# pcb10_5.net
KiCad netlist of a schematic drawn in EAGLE
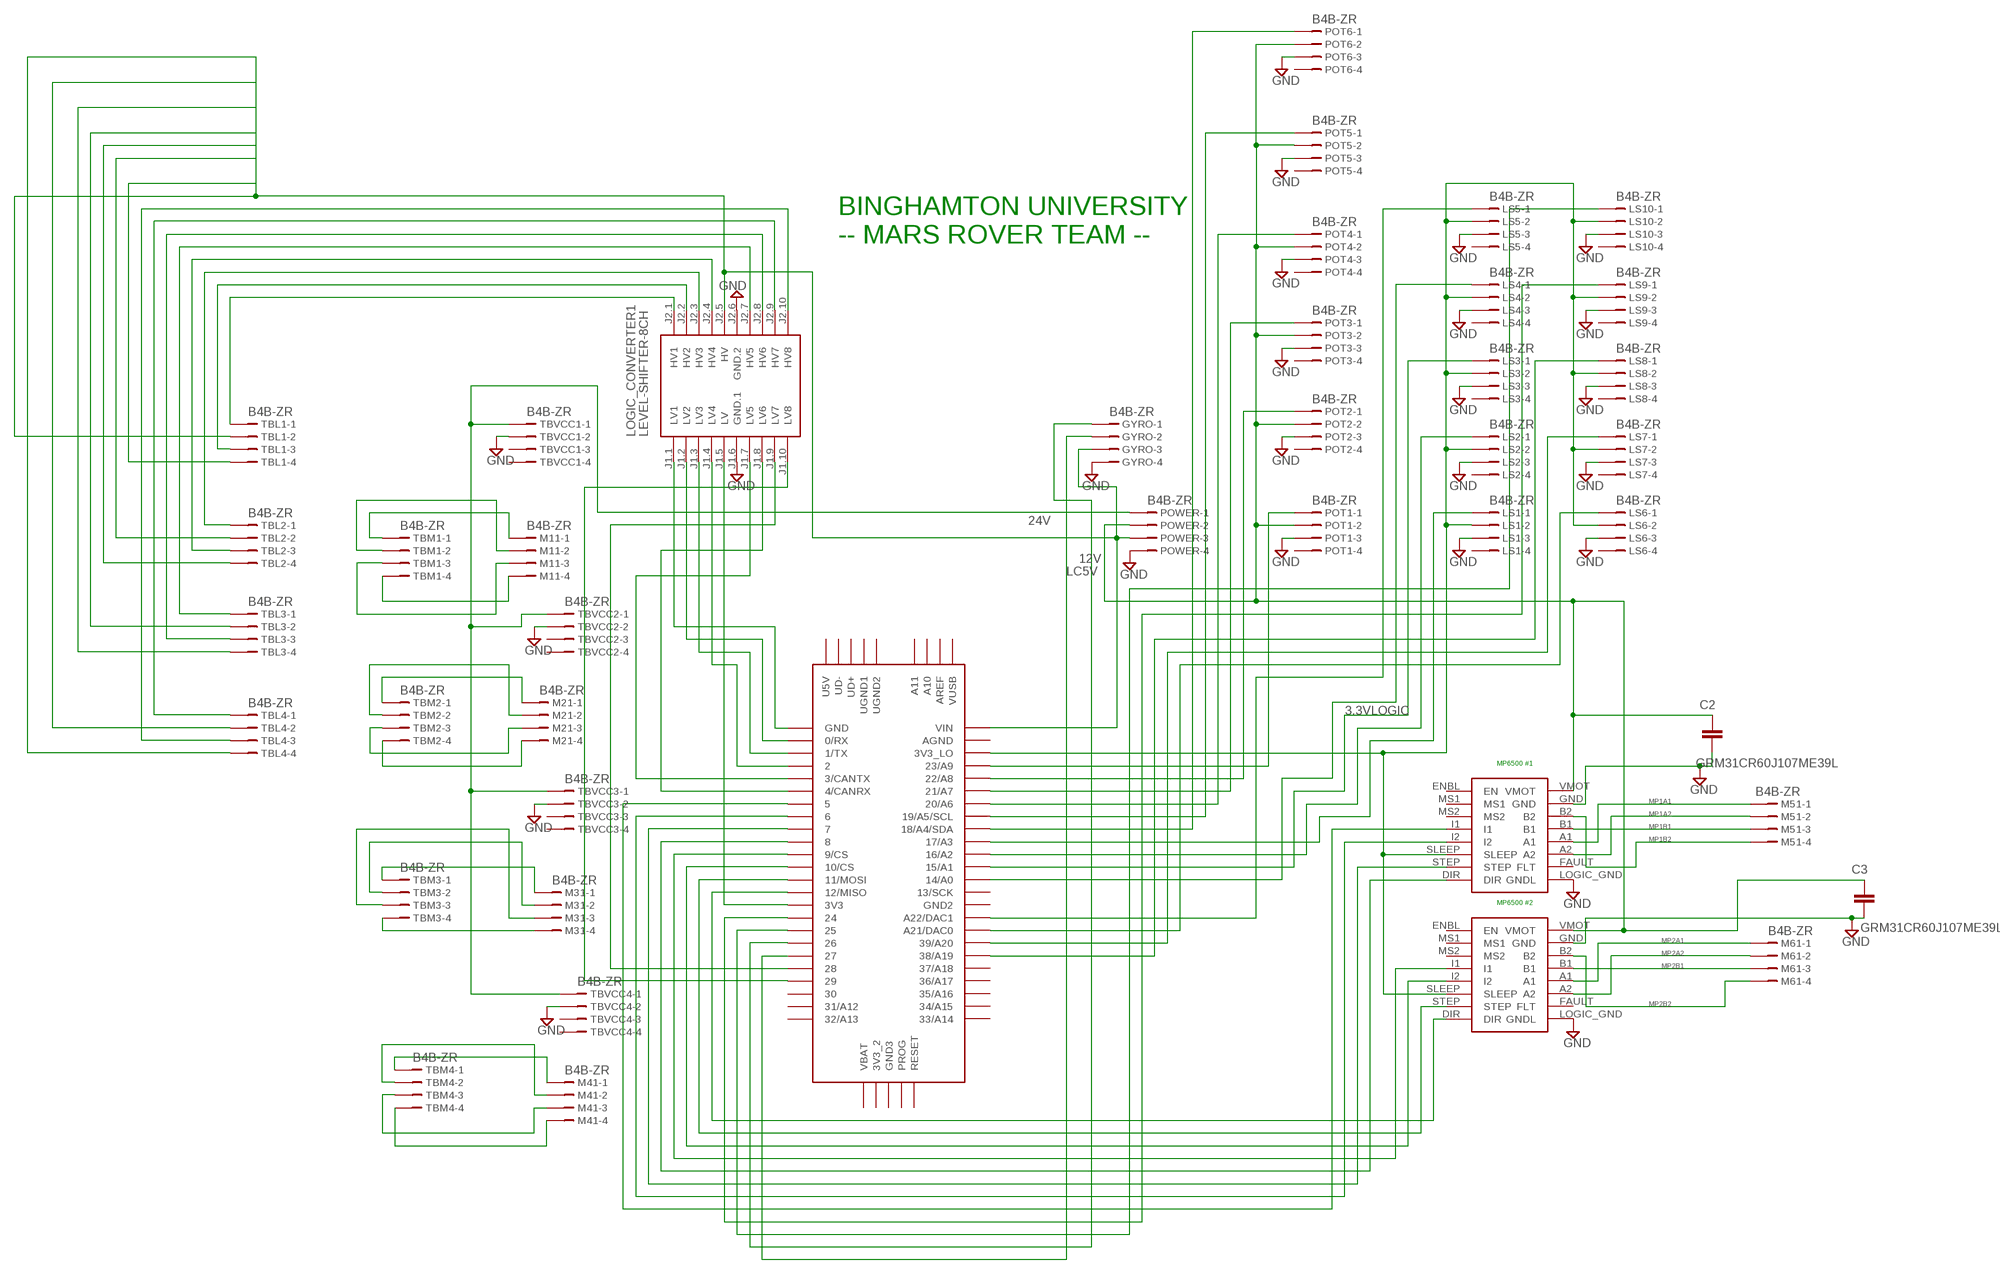
[diagram p0: schematic, sheet 1]

(export (version "E")
  (design (tool "Eeschema 10.0.6"))
  (components
    (comp (ref "C2")
      (value "GRM31CR60J107ME39L")
      (footprint "eagle-import:CAP_1206")
      (fields
        (field (name "MANUFACTURER") "Murata Electronics North America")
        (field (name "CREATED_BY") "PCBLayout.com")
      )
      (libsource (lib "eagle-import") (part "GRM31CR60J107ME39L"))
    )
    (comp (ref "C3")
      (value "GRM31CR60J107ME39L")
      (footprint "eagle-import:CAP_1206")
      (fields
        (field (name "MANUFACTURER") "Murata Electronics North America")
        (field (name "CREATED_BY") "PCBLayout.com")
      )
      (libsource (lib "eagle-import") (part "GRM31CR60J107ME39L"))
    )
    (comp (ref "GYRO")
      (value "B4B-ZR")
      (footprint "eagle-import:B4B-ZR")
      (fields (field (name "MF") "FARNELL") (field (name "MPN") "B4B-ZR(LF)(SN)"))
      (libsource (lib "eagle-import") (part "?4B-ZRB"))
    )
    (comp (ref "LOGIC_CONVERTER1")
      (value "LEVEL-SHIFTER-8CH")
      (footprint "eagle-import:LEVEL-SHIFTER-8CH")
      (libsource (lib "eagle-import") (part "LEVEL-SHIFTER-8CH"))
    )
    (comp (ref "LS1")
      (value "B4B-ZR")
      (footprint "eagle-import:B4B-ZR")
      (fields (field (name "MF") "FARNELL") (field (name "MPN") "B4B-ZR(LF)(SN)"))
      (libsource (lib "eagle-import") (part "?4B-ZRB"))
    )
    (comp (ref "LS2")
      (value "B4B-ZR")
      (footprint "eagle-import:B4B-ZR")
      (fields (field (name "MF") "FARNELL") (field (name "MPN") "B4B-ZR(LF)(SN)"))
      (libsource (lib "eagle-import") (part "?4B-ZRB"))
    )
    (comp (ref "LS3")
      (value "B4B-ZR")
      (footprint "eagle-import:B4B-ZR")
      (fields (field (name "MF") "FARNELL") (field (name "MPN") "B4B-ZR(LF)(SN)"))
      (libsource (lib "eagle-import") (part "?4B-ZRB"))
    )
    (comp (ref "LS4")
      (value "B4B-ZR")
      (footprint "eagle-import:B4B-ZR")
      (fields (field (name "MF") "FARNELL") (field (name "MPN") "B4B-ZR(LF)(SN)"))
      (libsource (lib "eagle-import") (part "?4B-ZRB"))
    )
    (comp (ref "LS5")
      (value "B4B-ZR")
      (footprint "eagle-import:B4B-ZR")
      (fields (field (name "MF") "FARNELL") (field (name "MPN") "B4B-ZR(LF)(SN)"))
      (libsource (lib "eagle-import") (part "?4B-ZRB"))
    )
    (comp (ref "LS6")
      (value "B4B-ZR")
      (footprint "eagle-import:B4B-ZR")
      (fields (field (name "MF") "FARNELL") (field (name "MPN") "B4B-ZR(LF)(SN)"))
      (libsource (lib "eagle-import") (part "?4B-ZRB"))
    )
    (comp (ref "LS7")
      (value "B4B-ZR")
      (footprint "eagle-import:B4B-ZR")
      (fields (field (name "MF") "FARNELL") (field (name "MPN") "B4B-ZR(LF)(SN)"))
      (libsource (lib "eagle-import") (part "?4B-ZRB"))
    )
    (comp (ref "LS8")
      (value "B4B-ZR")
      (footprint "eagle-import:B4B-ZR")
      (fields (field (name "MF") "FARNELL") (field (name "MPN") "B4B-ZR(LF)(SN)"))
      (libsource (lib "eagle-import") (part "?4B-ZRB"))
    )
    (comp (ref "LS9")
      (value "B4B-ZR")
      (footprint "eagle-import:B4B-ZR")
      (fields (field (name "MF") "FARNELL") (field (name "MPN") "B4B-ZR(LF)(SN)"))
      (libsource (lib "eagle-import") (part "?4B-ZRB"))
    )
    (comp (ref "LS10")
      (value "B4B-ZR")
      (footprint "eagle-import:B4B-ZR")
      (fields (field (name "MF") "FARNELL") (field (name "MPN") "B4B-ZR(LF)(SN)"))
      (libsource (lib "eagle-import") (part "?4B-ZRB"))
    )
    (comp (ref "M11")
      (value "B4B-ZR")
      (footprint "eagle-import:B4B-ZR")
      (fields (field (name "MF") "FARNELL") (field (name "MPN") "B4B-ZR(LF)(SN)"))
      (libsource (lib "eagle-import") (part "?4B-ZRB"))
    )
    (comp (ref "M21")
      (value "B4B-ZR")
      (footprint "eagle-import:B4B-ZR")
      (fields (field (name "MF") "FARNELL") (field (name "MPN") "B4B-ZR(LF)(SN)"))
      (libsource (lib "eagle-import") (part "?4B-ZRB"))
    )
    (comp (ref "M31")
      (value "B4B-ZR")
      (footprint "eagle-import:B4B-ZR")
      (fields (field (name "MF") "FARNELL") (field (name "MPN") "B4B-ZR(LF)(SN)"))
      (libsource (lib "eagle-import") (part "?4B-ZRB"))
    )
    (comp (ref "M41")
      (value "B4B-ZR")
      (footprint "eagle-import:B4B-ZR")
      (fields (field (name "MF") "FARNELL") (field (name "MPN") "B4B-ZR(LF)(SN)"))
      (libsource (lib "eagle-import") (part "?4B-ZRB"))
    )
    (comp (ref "M51")
      (value "B4B-ZR")
      (footprint "eagle-import:B4B-ZR")
      (fields (field (name "MF") "FARNELL") (field (name "MPN") "B4B-ZR(LF)(SN)"))
      (libsource (lib "eagle-import") (part "?4B-ZRB"))
    )
    (comp (ref "M61")
      (value "B4B-ZR")
      (footprint "eagle-import:B4B-ZR")
      (fields (field (name "MF") "FARNELL") (field (name "MPN") "B4B-ZR(LF)(SN)"))
      (libsource (lib "eagle-import") (part "?4B-ZRB"))
    )
    (comp (ref "MP6500_3")
      (value "MP6500THROUGH_HOLE")
      (footprint "eagle-import:MP6500")
      (libsource (lib "eagle-import") (part "MP6500THROUGH_HOLE"))
    )
    (comp (ref "MP6500_4")
      (value "MP6500THROUGH_HOLE")
      (footprint "eagle-import:MP6500")
      (libsource (lib "eagle-import") (part "MP6500THROUGH_HOLE"))
    )
    (comp (ref "POT1")
      (value "B4B-ZR")
      (footprint "eagle-import:B4B-ZR")
      (fields (field (name "MF") "FARNELL") (field (name "MPN") "B4B-ZR(LF)(SN)"))
      (libsource (lib "eagle-import") (part "?4B-ZRB"))
    )
    (comp (ref "POT2")
      (value "B4B-ZR")
      (footprint "eagle-import:B4B-ZR")
      (fields (field (name "MF") "FARNELL") (field (name "MPN") "B4B-ZR(LF)(SN)"))
      (libsource (lib "eagle-import") (part "?4B-ZRB"))
    )
    (comp (ref "POT3")
      (value "B4B-ZR")
      (footprint "eagle-import:B4B-ZR")
      (fields (field (name "MF") "FARNELL") (field (name "MPN") "B4B-ZR(LF)(SN)"))
      (libsource (lib "eagle-import") (part "?4B-ZRB"))
    )
    (comp (ref "POT4")
      (value "B4B-ZR")
      (footprint "eagle-import:B4B-ZR")
      (fields (field (name "MF") "FARNELL") (field (name "MPN") "B4B-ZR(LF)(SN)"))
      (libsource (lib "eagle-import") (part "?4B-ZRB"))
    )
    (comp (ref "POT5")
      (value "B4B-ZR")
      (footprint "eagle-import:B4B-ZR")
      (fields (field (name "MF") "FARNELL") (field (name "MPN") "B4B-ZR(LF)(SN)"))
      (libsource (lib "eagle-import") (part "?4B-ZRB"))
    )
    (comp (ref "POT6")
      (value "B4B-ZR")
      (footprint "eagle-import:B4B-ZR")
      (fields (field (name "MF") "FARNELL") (field (name "MPN") "B4B-ZR(LF)(SN)"))
      (libsource (lib "eagle-import") (part "?4B-ZRB"))
    )
    (comp (ref "POWER")
      (value "B4B-ZR")
      (footprint "eagle-import:B4B-ZR")
      (fields (field (name "MF") "FARNELL") (field (name "MPN") "B4B-ZR(LF)(SN)"))
      (libsource (lib "eagle-import") (part "?4B-ZRB"))
    )
    (comp (ref "TBL1")
      (value "B4B-ZR")
      (footprint "eagle-import:B4B-ZR")
      (fields (field (name "MF") "FARNELL") (field (name "MPN") "B4B-ZR(LF)(SN)"))
      (libsource (lib "eagle-import") (part "?4B-ZRB"))
    )
    (comp (ref "TBL2")
      (value "B4B-ZR")
      (footprint "eagle-import:B4B-ZR")
      (fields (field (name "MF") "FARNELL") (field (name "MPN") "B4B-ZR(LF)(SN)"))
      (libsource (lib "eagle-import") (part "?4B-ZRB"))
    )
    (comp (ref "TBL3")
      (value "B4B-ZR")
      (footprint "eagle-import:B4B-ZR")
      (fields (field (name "MF") "FARNELL") (field (name "MPN") "B4B-ZR(LF)(SN)"))
      (libsource (lib "eagle-import") (part "?4B-ZRB"))
    )
    (comp (ref "TBL4")
      (value "B4B-ZR")
      (footprint "eagle-import:B4B-ZR")
      (fields (field (name "MF") "FARNELL") (field (name "MPN") "B4B-ZR(LF)(SN)"))
      (libsource (lib "eagle-import") (part "?4B-ZRB"))
    )
    (comp (ref "TBM1")
      (value "B4B-ZR")
      (footprint "eagle-import:B4B-ZR")
      (fields (field (name "MF") "FARNELL") (field (name "MPN") "B4B-ZR(LF)(SN)"))
      (libsource (lib "eagle-import") (part "?4B-ZRB"))
    )
    (comp (ref "TBM2")
      (value "B4B-ZR")
      (footprint "eagle-import:B4B-ZR")
      (fields (field (name "MF") "FARNELL") (field (name "MPN") "B4B-ZR(LF)(SN)"))
      (libsource (lib "eagle-import") (part "?4B-ZRB"))
    )
    (comp (ref "TBM3")
      (value "B4B-ZR")
      (footprint "eagle-import:B4B-ZR")
      (fields (field (name "MF") "FARNELL") (field (name "MPN") "B4B-ZR(LF)(SN)"))
      (libsource (lib "eagle-import") (part "?4B-ZRB"))
    )
    (comp (ref "TBM4")
      (value "B4B-ZR")
      (footprint "eagle-import:B4B-ZR")
      (fields (field (name "MF") "FARNELL") (field (name "MPN") "B4B-ZR(LF)(SN)"))
      (libsource (lib "eagle-import") (part "?4B-ZRB"))
    )
    (comp (ref "TBVCC1")
      (value "B4B-ZR")
      (footprint "eagle-import:B4B-ZR")
      (fields (field (name "MF") "FARNELL") (field (name "MPN") "B4B-ZR(LF)(SN)"))
      (libsource (lib "eagle-import") (part "?4B-ZRB"))
    )
    (comp (ref "TBVCC2")
      (value "B4B-ZR")
      (footprint "eagle-import:B4B-ZR")
      (fields (field (name "MF") "FARNELL") (field (name "MPN") "B4B-ZR(LF)(SN)"))
      (libsource (lib "eagle-import") (part "?4B-ZRB"))
    )
    (comp (ref "TBVCC3")
      (value "B4B-ZR")
      (footprint "eagle-import:B4B-ZR")
      (fields (field (name "MF") "FARNELL") (field (name "MPN") "B4B-ZR(LF)(SN)"))
      (libsource (lib "eagle-import") (part "?4B-ZRB"))
    )
    (comp (ref "TBVCC4")
      (value "B4B-ZR")
      (footprint "eagle-import:B4B-ZR")
      (fields (field (name "MF") "FARNELL") (field (name "MPN") "B4B-ZR(LF)(SN)"))
      (libsource (lib "eagle-import") (part "?4B-ZRB"))
    )
    (comp (ref "TEENSY4.2")
      (value "TEENSY_3.5/3.6")
      (footprint "eagle-import:TEENSY_3.5_3.6")
      (libsource (lib "eagle-import") (part "TEENSY_3.5/3.6"))
    )
  )
  (nets
    (net (code "1") (name "/3.3VLOGIC") (class "Default")
      (node (ref "LS1") (pin "2") (pinfunction "1_2") (pintype "passive"))
      (node (ref "LS10") (pin "2") (pinfunction "1_2") (pintype "passive"))
      (node (ref "LS2") (pin "2") (pinfunction "1_2") (pintype "passive"))
      (node (ref "LS3") (pin "2") (pinfunction "1_2") (pintype "passive"))
      (node (ref "LS4") (pin "2") (pinfunction "1_2") (pintype "passive"))
      (node (ref "LS5") (pin "2") (pinfunction "1_2") (pintype "passive"))
      (node (ref "LS6") (pin "2") (pinfunction "1_2") (pintype "passive"))
      (node (ref "LS7") (pin "2") (pinfunction "1_2") (pintype "passive"))
      (node (ref "LS8") (pin "2") (pinfunction "1_2") (pintype "passive"))
      (node (ref "LS9") (pin "2") (pinfunction "1_2") (pintype "passive"))
      (node (ref "MP6500_3") (pin "SLEEP") (pinfunction "SLEEP_SLEEP") (pintype "bidirectional"))
      (node (ref "MP6500_4") (pin "SLEEP") (pinfunction "SLEEP_SLEEP") (pintype "bidirectional"))
      (node (ref "TEENSY4.2") (pin "3V3_LO") (pinfunction "3V3_LO_3V3_LO") (pintype "bidirectional"))
    )
    (net (code "2") (name "/12V") (class "Default")
      (node (ref "C2") (pin "1") (pinfunction "1_1") (pintype "passive"))
      (node (ref "C3") (pin "1") (pinfunction "1_1") (pintype "passive"))
      (node (ref "MP6500_3") (pin "VMOT") (pinfunction "VMOT_VMOT") (pintype "bidirectional"))
      (node (ref "MP6500_4") (pin "VMOT") (pinfunction "VMOT_VMOT") (pintype "bidirectional"))
      (node (ref "POT1") (pin "2") (pinfunction "1_2") (pintype "passive"))
      (node (ref "POT2") (pin "2") (pinfunction "1_2") (pintype "passive"))
      (node (ref "POT3") (pin "2") (pinfunction "1_2") (pintype "passive"))
      (node (ref "POT4") (pin "2") (pinfunction "1_2") (pintype "passive"))
      (node (ref "POT5") (pin "2") (pinfunction "1_2") (pintype "passive"))
      (node (ref "POT6") (pin "2") (pinfunction "1_2") (pintype "passive"))
      (node (ref "POWER") (pin "2") (pinfunction "1_2") (pintype "passive"))
    )
    (net (code "3") (name "/24V") (class "Default")
      (node (ref "POWER") (pin "1") (pinfunction "1_1") (pintype "passive"))
      (node (ref "TBVCC1") (pin "1") (pinfunction "1_1") (pintype "passive"))
      (node (ref "TBVCC2") (pin "1") (pinfunction "1_1") (pintype "passive"))
      (node (ref "TBVCC3") (pin "1") (pinfunction "1_1") (pintype "passive"))
      (node (ref "TBVCC4") (pin "1") (pinfunction "1_1") (pintype "passive"))
    )
    (net (code "4") (name "/LC5V") (class "Default")
      (node (ref "GYRO") (pin "3") (pinfunction "1_3") (pintype "passive"))
      (node (ref "LOGIC_CONVERTER1") (pin "J2.5") (pinfunction "HV_J2.5") (pintype "power_in"))
      (node (ref "POWER") (pin "3") (pinfunction "1_3") (pintype "passive"))
      (node (ref "TBL1") (pin "2") (pinfunction "1_2") (pintype "passive"))
      (node (ref "TBL1") (pin "4") (pinfunction "1_4") (pintype "passive"))
      (node (ref "TBL2") (pin "2") (pinfunction "1_2") (pintype "passive"))
      (node (ref "TBL2") (pin "4") (pinfunction "1_4") (pintype "passive"))
      (node (ref "TBL3") (pin "2") (pinfunction "1_2") (pintype "passive"))
      (node (ref "TBL3") (pin "4") (pinfunction "1_4") (pintype "passive"))
      (node (ref "TBL4") (pin "2") (pinfunction "1_2") (pintype "passive"))
      (node (ref "TBL4") (pin "4") (pinfunction "1_4") (pintype "passive"))
      (node (ref "TEENSY4.2") (pin "VIN") (pinfunction "VIN_VIN") (pintype "bidirectional"))
    )
    (net (code "5") (name "/MP1A1") (class "Default")
      (node (ref "M51") (pin "1") (pinfunction "1_1") (pintype "passive"))
      (node (ref "MP6500_3") (pin "A1") (pinfunction "A1_A1") (pintype "bidirectional"))
    )
    (net (code "6") (name "/MP1A2") (class "Default")
      (node (ref "M51") (pin "2") (pinfunction "1_2") (pintype "passive"))
      (node (ref "MP6500_3") (pin "A2") (pinfunction "A2_A2") (pintype "bidirectional"))
    )
    (net (code "7") (name "/MP1B1") (class "Default")
      (node (ref "M51") (pin "3") (pinfunction "1_3") (pintype "passive"))
      (node (ref "MP6500_3") (pin "B1") (pinfunction "B1_B1") (pintype "bidirectional"))
    )
    (net (code "8") (name "/MP1B2") (class "Default")
      (node (ref "M51") (pin "4") (pinfunction "1_4") (pintype "passive"))
      (node (ref "MP6500_3") (pin "B2") (pinfunction "B2_B2") (pintype "bidirectional"))
    )
    (net (code "9") (name "/MP2A1") (class "Default")
      (node (ref "M61") (pin "1") (pinfunction "1_1") (pintype "passive"))
      (node (ref "MP6500_4") (pin "A1") (pinfunction "A1_A1") (pintype "bidirectional"))
    )
    (net (code "10") (name "/MP2A2") (class "Default")
      (node (ref "M61") (pin "2") (pinfunction "1_2") (pintype "passive"))
      (node (ref "MP6500_4") (pin "A2") (pinfunction "A2_A2") (pintype "bidirectional"))
    )
    (net (code "11") (name "/MP2B1") (class "Default")
      (node (ref "M61") (pin "3") (pinfunction "1_3") (pintype "passive"))
      (node (ref "MP6500_4") (pin "B1") (pinfunction "B1_B1") (pintype "bidirectional"))
    )
    (net (code "12") (name "/MP2B2") (class "Default")
      (node (ref "M61") (pin "4") (pinfunction "1_4") (pintype "passive"))
      (node (ref "MP6500_4") (pin "B2") (pinfunction "B2_B2") (pintype "bidirectional"))
    )
    (net (code "13") (name "GND") (class "Default")
      (node (ref "C2") (pin "2") (pinfunction "2_2") (pintype "passive"))
      (node (ref "C3") (pin "2") (pinfunction "2_2") (pintype "passive"))
      (node (ref "GYRO") (pin "4") (pinfunction "1_4") (pintype "passive"))
      (node (ref "LOGIC_CONVERTER1") (pin "J1.6") (pinfunction "GND.1_J1.6") (pintype "power_in"))
      (node (ref "LOGIC_CONVERTER1") (pin "J2.6") (pinfunction "GND.2_J2.6") (pintype "power_in"))
      (node (ref "LS1") (pin "3") (pinfunction "1_3") (pintype "passive"))
      (node (ref "LS10") (pin "3") (pinfunction "1_3") (pintype "passive"))
      (node (ref "LS2") (pin "3") (pinfunction "1_3") (pintype "passive"))
      (node (ref "LS3") (pin "3") (pinfunction "1_3") (pintype "passive"))
      (node (ref "LS4") (pin "3") (pinfunction "1_3") (pintype "passive"))
      (node (ref "LS5") (pin "3") (pinfunction "1_3") (pintype "passive"))
      (node (ref "LS6") (pin "3") (pinfunction "1_3") (pintype "passive"))
      (node (ref "LS7") (pin "3") (pinfunction "1_3") (pintype "passive"))
      (node (ref "LS8") (pin "3") (pinfunction "1_3") (pintype "passive"))
      (node (ref "LS9") (pin "3") (pinfunction "1_3") (pintype "passive"))
      (node (ref "MP6500_3") (pin "GND") (pinfunction "GND_GND") (pintype "bidirectional"))
      (node (ref "MP6500_3") (pin "LOGIC_GND") (pinfunction "GNDL_LOGIC_GND") (pintype "bidirectional"))
      (node (ref "MP6500_4") (pin "GND") (pinfunction "GND_GND") (pintype "bidirectional"))
      (node (ref "MP6500_4") (pin "LOGIC_GND") (pinfunction "GNDL_LOGIC_GND") (pintype "bidirectional"))
      (node (ref "POT1") (pin "3") (pinfunction "1_3") (pintype "passive"))
      (node (ref "POT2") (pin "3") (pinfunction "1_3") (pintype "passive"))
      (node (ref "POT3") (pin "3") (pinfunction "1_3") (pintype "passive"))
      (node (ref "POT4") (pin "3") (pinfunction "1_3") (pintype "passive"))
      (node (ref "POT5") (pin "3") (pinfunction "1_3") (pintype "passive"))
      (node (ref "POT6") (pin "3") (pinfunction "1_3") (pintype "passive"))
      (node (ref "POWER") (pin "4") (pinfunction "1_4") (pintype "passive"))
      (node (ref "TBVCC1") (pin "2") (pinfunction "1_2") (pintype "passive"))
      (node (ref "TBVCC2") (pin "2") (pinfunction "1_2") (pintype "passive"))
      (node (ref "TBVCC3") (pin "2") (pinfunction "1_2") (pintype "passive"))
      (node (ref "TBVCC4") (pin "2") (pinfunction "1_2") (pintype "passive"))
    )
    (net (code "14") (name "Net-(GYRO-Pad1)") (class "Default")
      (node (ref "GYRO") (pin "1") (pinfunction "1_1") (pintype "passive"))
      (node (ref "TEENSY4.2") (pin "26") (pinfunction "26_26") (pintype "bidirectional"))
    )
    (net (code "15") (name "Net-(GYROB-1)") (class "Default")
      (node (ref "GYRO") (pin "2") (pinfunction "1_2") (pintype "passive"))
      (node (ref "TEENSY4.2") (pin "27") (pinfunction "27_27") (pintype "bidirectional"))
    )
    (net (code "16") (name "Net-(LOGIC_CONVERTER1-HV1)") (class "Default")
      (node (ref "LOGIC_CONVERTER1") (pin "J2.1") (pinfunction "HV1_J2.1") (pintype "bidirectional"))
      (node (ref "TBL1") (pin "1") (pinfunction "1_1") (pintype "passive"))
    )
    (net (code "17") (name "Net-(LOGIC_CONVERTER1-HV2)") (class "Default")
      (node (ref "LOGIC_CONVERTER1") (pin "J2.2") (pinfunction "HV2_J2.2") (pintype "bidirectional"))
      (node (ref "TBL1") (pin "3") (pinfunction "1_3") (pintype "passive"))
    )
    (net (code "18") (name "Net-(LOGIC_CONVERTER1-HV3)") (class "Default")
      (node (ref "LOGIC_CONVERTER1") (pin "J2.3") (pinfunction "HV3_J2.3") (pintype "bidirectional"))
      (node (ref "TBL2") (pin "1") (pinfunction "1_1") (pintype "passive"))
    )
    (net (code "19") (name "Net-(LOGIC_CONVERTER1-HV4)") (class "Default")
      (node (ref "LOGIC_CONVERTER1") (pin "J2.4") (pinfunction "HV4_J2.4") (pintype "bidirectional"))
      (node (ref "TBL2") (pin "3") (pinfunction "1_3") (pintype "passive"))
    )
    (net (code "20") (name "Net-(LOGIC_CONVERTER1-HV5)") (class "Default")
      (node (ref "LOGIC_CONVERTER1") (pin "J2.7") (pinfunction "HV5_J2.7") (pintype "bidirectional"))
      (node (ref "TBL3") (pin "1") (pinfunction "1_1") (pintype "passive"))
    )
    (net (code "21") (name "Net-(LOGIC_CONVERTER1-HV6)") (class "Default")
      (node (ref "LOGIC_CONVERTER1") (pin "J2.8") (pinfunction "HV6_J2.8") (pintype "bidirectional"))
      (node (ref "TBL3") (pin "3") (pinfunction "1_3") (pintype "passive"))
    )
    (net (code "22") (name "Net-(LOGIC_CONVERTER1-HV7)") (class "Default")
      (node (ref "LOGIC_CONVERTER1") (pin "J2.9") (pinfunction "HV7_J2.9") (pintype "bidirectional"))
      (node (ref "TBL4") (pin "1") (pinfunction "1_1") (pintype "passive"))
    )
    (net (code "23") (name "Net-(LOGIC_CONVERTER1-HV8)") (class "Default")
      (node (ref "LOGIC_CONVERTER1") (pin "J2.10") (pinfunction "HV8_J2.10") (pintype "bidirectional"))
      (node (ref "TBL4") (pin "3") (pinfunction "1_3") (pintype "passive"))
    )
    (net (code "24") (name "Net-(LOGIC_CONVERTER1-LV)") (class "Default")
      (node (ref "LOGIC_CONVERTER1") (pin "J1.5") (pinfunction "LV_J1.5") (pintype "power_in"))
      (node (ref "TEENSY4.2") (pin "3V3") (pinfunction "3V3_3V3") (pintype "bidirectional"))
    )
    (net (code "25") (name "Net-(LOGIC_CONVERTER1-LV1)") (class "Default")
      (node (ref "LOGIC_CONVERTER1") (pin "J1.1") (pinfunction "LV1_J1.1") (pintype "bidirectional"))
      (node (ref "TEENSY4.2") (pin "GND") (pinfunction "GND_GND") (pintype "bidirectional"))
    )
    (net (code "26") (name "Net-(LOGIC_CONVERTER1-LV2)") (class "Default")
      (node (ref "LOGIC_CONVERTER1") (pin "J1.2") (pinfunction "LV2_J1.2") (pintype "bidirectional"))
      (node (ref "TEENSY4.2") (pin "0/RX") (pinfunction "0/RX_0/RX") (pintype "bidirectional"))
    )
    (net (code "27") (name "Net-(LOGIC_CONVERTER1-LV3)") (class "Default")
      (node (ref "LOGIC_CONVERTER1") (pin "J1.3") (pinfunction "LV3_J1.3") (pintype "bidirectional"))
      (node (ref "TEENSY4.2") (pin "1/TX") (pinfunction "1/TX_1/TX") (pintype "bidirectional"))
    )
    (net (code "28") (name "Net-(LOGIC_CONVERTER1-LV4)") (class "Default")
      (node (ref "LOGIC_CONVERTER1") (pin "J1.4") (pinfunction "LV4_J1.4") (pintype "bidirectional"))
      (node (ref "TEENSY4.2") (pin "2") (pinfunction "2_2") (pintype "bidirectional"))
    )
    (net (code "29") (name "Net-(LOGIC_CONVERTER1-LV5)") (class "Default")
      (node (ref "LOGIC_CONVERTER1") (pin "J1.7") (pinfunction "LV5_J1.7") (pintype "bidirectional"))
      (node (ref "TEENSY4.2") (pin "3/CANTX") (pinfunction "3/CANTX_3/CANTX") (pintype "bidirectional"))
    )
    (net (code "30") (name "Net-(LOGIC_CONVERTER1-LV6)") (class "Default")
      (node (ref "LOGIC_CONVERTER1") (pin "J1.8") (pinfunction "LV6_J1.8") (pintype "bidirectional"))
      (node (ref "TEENSY4.2") (pin "4/CANRX") (pinfunction "4/CANRX_4/CANRX") (pintype "bidirectional"))
    )
    (net (code "31") (name "Net-(LOGIC_CONVERTER1-LV7)") (class "Default")
      (node (ref "LOGIC_CONVERTER1") (pin "J1.9") (pinfunction "LV7_J1.9") (pintype "bidirectional"))
      (node (ref "TEENSY4.2") (pin "28") (pinfunction "28_28") (pintype "bidirectional"))
    )
    (net (code "32") (name "Net-(LOGIC_CONVERTER1-LV8)") (class "Default")
      (node (ref "LOGIC_CONVERTER1") (pin "J1.10") (pinfunction "LV8_J1.10") (pintype "bidirectional"))
      (node (ref "TEENSY4.2") (pin "29") (pinfunction "29_29") (pintype "bidirectional"))
    )
    (net (code "33") (name "Net-(LS1-Pad1)") (class "Default")
      (node (ref "LS1") (pin "1") (pinfunction "1_1") (pintype "passive"))
      (node (ref "TEENSY4.2") (pin "17/A3") (pinfunction "17/A3_17/A3") (pintype "bidirectional"))
    )
    (net (code "34") (name "Net-(LS2-Pad1)") (class "Default")
      (node (ref "LS2") (pin "1") (pinfunction "1_1") (pintype "passive"))
      (node (ref "TEENSY4.2") (pin "16/A2") (pinfunction "16/A2_16/A2") (pintype "bidirectional"))
    )
    (net (code "35") (name "Net-(LS3-Pad1)") (class "Default")
      (node (ref "LS3") (pin "1") (pinfunction "1_1") (pintype "passive"))
      (node (ref "TEENSY4.2") (pin "15/A1") (pinfunction "15/A1_15/A1") (pintype "bidirectional"))
    )
    (net (code "36") (name "Net-(LS4-Pad1)") (class "Default")
      (node (ref "LS4") (pin "1") (pinfunction "1_1") (pintype "passive"))
      (node (ref "TEENSY4.2") (pin "14/A0") (pinfunction "14/A0_14/A0") (pintype "bidirectional"))
    )
    (net (code "37") (name "Net-(LS5-Pad1)") (class "Default")
      (node (ref "LS5") (pin "1") (pinfunction "1_1") (pintype "passive"))
      (node (ref "TEENSY4.2") (pin "A22/DAC1") (pinfunction "A22/DAC1_A22/DAC1") (pintype "bidirectional"))
    )
    (net (code "38") (name "Net-(LS7-Pad1)") (class "Default")
      (node (ref "LS7") (pin "1") (pinfunction "1_1") (pintype "passive"))
      (node (ref "TEENSY4.2") (pin "39/A20") (pinfunction "39/A20_39/A20") (pintype "bidirectional"))
    )
    (net (code "39") (name "Net-(LS8-Pad1)") (class "Default")
      (node (ref "LS8") (pin "1") (pinfunction "1_1") (pintype "passive"))
      (node (ref "TEENSY4.2") (pin "38/A19") (pinfunction "38/A19_38/A19") (pintype "bidirectional"))
    )
    (net (code "40") (name "Net-(LS9-Pad1)") (class "Default")
      (node (ref "LS9") (pin "1") (pinfunction "1_1") (pintype "passive"))
      (node (ref "TEENSY4.2") (pin "24") (pinfunction "24_24") (pintype "bidirectional"))
    )
    (net (code "41") (name "Net-(LS10-Pad1)") (class "Default")
      (node (ref "LS10") (pin "1") (pinfunction "1_1") (pintype "passive"))
      (node (ref "TEENSY4.2") (pin "25") (pinfunction "25_25") (pintype "bidirectional"))
    )
    (net (code "42") (name "Net-(M11-Pad1)") (class "Default")
      (node (ref "M11") (pin "1") (pinfunction "1_1") (pintype "passive"))
      (node (ref "TBM1") (pin "1") (pinfunction "1_1") (pintype "passive"))
    )
    (net (code "43") (name "Net-(M11B-1)") (class "Default")
      (node (ref "M11") (pin "2") (pinfunction "1_2") (pintype "passive"))
      (node (ref "TBM1") (pin "2") (pinfunction "1_2") (pintype "passive"))
    )
    (net (code "44") (name "Net-(M11C-1)") (class "Default")
      (node (ref "M11") (pin "3") (pinfunction "1_3") (pintype "passive"))
      (node (ref "TBM1") (pin "3") (pinfunction "1_3") (pintype "passive"))
    )
    (net (code "45") (name "Net-(M11D-1)") (class "Default")
      (node (ref "M11") (pin "4") (pinfunction "1_4") (pintype "passive"))
      (node (ref "TBM1") (pin "4") (pinfunction "1_4") (pintype "passive"))
    )
    (net (code "46") (name "Net-(M21-Pad1)") (class "Default")
      (node (ref "M21") (pin "1") (pinfunction "1_1") (pintype "passive"))
      (node (ref "TBM2") (pin "1") (pinfunction "1_1") (pintype "passive"))
    )
    (net (code "47") (name "Net-(M21B-1)") (class "Default")
      (node (ref "M21") (pin "2") (pinfunction "1_2") (pintype "passive"))
      (node (ref "TBM2") (pin "2") (pinfunction "1_2") (pintype "passive"))
    )
    (net (code "48") (name "Net-(M21C-1)") (class "Default")
      (node (ref "M21") (pin "3") (pinfunction "1_3") (pintype "passive"))
      (node (ref "TBM2") (pin "3") (pinfunction "1_3") (pintype "passive"))
    )
    (net (code "49") (name "Net-(M21D-1)") (class "Default")
      (node (ref "M21") (pin "4") (pinfunction "1_4") (pintype "passive"))
      (node (ref "TBM2") (pin "4") (pinfunction "1_4") (pintype "passive"))
    )
    (net (code "50") (name "Net-(M31-Pad1)") (class "Default")
      (node (ref "M31") (pin "1") (pinfunction "1_1") (pintype "passive"))
      (node (ref "TBM3") (pin "1") (pinfunction "1_1") (pintype "passive"))
    )
    (net (code "51") (name "Net-(M31B-1)") (class "Default")
      (node (ref "M31") (pin "2") (pinfunction "1_2") (pintype "passive"))
      (node (ref "TBM3") (pin "2") (pinfunction "1_2") (pintype "passive"))
    )
    (net (code "52") (name "Net-(M31C-1)") (class "Default")
      (node (ref "M31") (pin "3") (pinfunction "1_3") (pintype "passive"))
      (node (ref "TBM3") (pin "3") (pinfunction "1_3") (pintype "passive"))
    )
    (net (code "53") (name "Net-(M31D-1)") (class "Default")
      (node (ref "M31") (pin "4") (pinfunction "1_4") (pintype "passive"))
      (node (ref "TBM3") (pin "4") (pinfunction "1_4") (pintype "passive"))
    )
    (net (code "54") (name "Net-(M41-Pad1)") (class "Default")
      (node (ref "M41") (pin "1") (pinfunction "1_1") (pintype "passive"))
      (node (ref "TBM4") (pin "1") (pinfunction "1_1") (pintype "passive"))
    )
    (net (code "55") (name "Net-(M41B-1)") (class "Default")
      (node (ref "M41") (pin "2") (pinfunction "1_2") (pintype "passive"))
      (node (ref "TBM4") (pin "2") (pinfunction "1_2") (pintype "passive"))
    )
    (net (code "56") (name "Net-(M41C-1)") (class "Default")
      (node (ref "M41") (pin "3") (pinfunction "1_3") (pintype "passive"))
      (node (ref "TBM4") (pin "3") (pinfunction "1_3") (pintype "passive"))
    )
    (net (code "57") (name "Net-(M41D-1)") (class "Default")
      (node (ref "M41") (pin "4") (pinfunction "1_4") (pintype "passive"))
      (node (ref "TBM4") (pin "4") (pinfunction "1_4") (pintype "passive"))
    )
    (net (code "58") (name "Net-(MP6500_3-PadDIR)") (class "Default")
      (node (ref "MP6500_3") (pin "DIR") (pinfunction "DIR_DIR") (pintype "bidirectional"))
      (node (ref "TEENSY4.2") (pin "8") (pinfunction "8_8") (pintype "bidirectional"))
    )
    (net (code "59") (name "Net-(MP6500_3-PadI1)") (class "Default")
      (node (ref "MP6500_3") (pin "I1") (pinfunction "I1_I1") (pintype "bidirectional"))
      (node (ref "TEENSY4.2") (pin "5") (pinfunction "5_5") (pintype "bidirectional"))
    )
    (net (code "60") (name "Net-(MP6500_3-PadI2)") (class "Default")
      (node (ref "MP6500_3") (pin "I2") (pinfunction "I2_I2") (pintype "bidirectional"))
      (node (ref "TEENSY4.2") (pin "6") (pinfunction "6_6") (pintype "bidirectional"))
    )
    (net (code "61") (name "Net-(MP6500_3-PadSTEP)") (class "Default")
      (node (ref "MP6500_3") (pin "STEP") (pinfunction "STEP_STEP") (pintype "bidirectional"))
      (node (ref "TEENSY4.2") (pin "7") (pinfunction "7_7") (pintype "bidirectional"))
    )
    (net (code "62") (name "Net-(MP6500_4-PadDIR)") (class "Default")
      (node (ref "MP6500_4") (pin "DIR") (pinfunction "DIR_DIR") (pintype "bidirectional"))
      (node (ref "TEENSY4.2") (pin "12/MISO") (pinfunction "12/MISO_12/MISO") (pintype "bidirectional"))
    )
    (net (code "63") (name "Net-(MP6500_4-PadI1)") (class "Default")
      (node (ref "MP6500_4") (pin "I1") (pinfunction "I1_I1") (pintype "bidirectional"))
      (node (ref "TEENSY4.2") (pin "9/CS") (pinfunction "9/CS_9/CS") (pintype "bidirectional"))
    )
    (net (code "64") (name "Net-(MP6500_4-PadI2)") (class "Default")
      (node (ref "MP6500_4") (pin "I2") (pinfunction "I2_I2") (pintype "bidirectional"))
      (node (ref "TEENSY4.2") (pin "10/CS") (pinfunction "10/CS_10/CS") (pintype "bidirectional"))
    )
    (net (code "65") (name "Net-(MP6500_4-PadSTEP)") (class "Default")
      (node (ref "MP6500_4") (pin "STEP") (pinfunction "STEP_STEP") (pintype "bidirectional"))
      (node (ref "TEENSY4.2") (pin "11/MOSI") (pinfunction "11/MOSI_11/MOSI") (pintype "bidirectional"))
    )
    (net (code "66") (name "Net-(POT1-Pad1)") (class "Default")
      (node (ref "POT1") (pin "1") (pinfunction "1_1") (pintype "passive"))
      (node (ref "TEENSY4.2") (pin "23/A9") (pinfunction "23/A9_23/A9") (pintype "bidirectional"))
    )
    (net (code "67") (name "Net-(POT2-Pad1)") (class "Default")
      (node (ref "POT2") (pin "1") (pinfunction "1_1") (pintype "passive"))
      (node (ref "TEENSY4.2") (pin "22/A8") (pinfunction "22/A8_22/A8") (pintype "bidirectional"))
    )
    (net (code "68") (name "Net-(POT3-Pad1)") (class "Default")
      (node (ref "POT3") (pin "1") (pinfunction "1_1") (pintype "passive"))
      (node (ref "TEENSY4.2") (pin "21/A7") (pinfunction "21/A7_21/A7") (pintype "bidirectional"))
    )
    (net (code "69") (name "Net-(POT4-Pad1)") (class "Default")
      (node (ref "POT4") (pin "1") (pinfunction "1_1") (pintype "passive"))
      (node (ref "TEENSY4.2") (pin "20/A6") (pinfunction "20/A6_20/A6") (pintype "bidirectional"))
    )
    (net (code "70") (name "Net-(POT5-Pad1)") (class "Default")
      (node (ref "POT5") (pin "1") (pinfunction "1_1") (pintype "passive"))
      (node (ref "TEENSY4.2") (pin "19/A5/SCL") (pinfunction "19/A5/SCL_19/A5/SCL") (pintype "bidirectional"))
    )
    (net (code "71") (name "Net-(POT6-Pad1)") (class "Default")
      (node (ref "POT6") (pin "1") (pinfunction "1_1") (pintype "passive"))
      (node (ref "TEENSY4.2") (pin "18/A4/SDA") (pinfunction "18/A4/SDA_18/A4/SDA") (pintype "bidirectional"))
    )
    (net (code "72") (name "Net-(TEENSY4.2-A21{slash}DAC0)") (class "Default")
      (node (ref "LS6") (pin "1") (pinfunction "1_1") (pintype "passive"))
      (node (ref "TEENSY4.2") (pin "21/DAC0") (pinfunction "A21/DAC0_21/DAC0") (pintype "bidirectional"))
    )
    (net (code "73") (name "unconnected-(LS1D-1-Pad4)") (class "Default")
      (node (ref "LS1") (pin "4") (pinfunction "1_4") (pintype "passive"))
    )
    (net (code "74") (name "unconnected-(LS2D-1-Pad4)") (class "Default")
      (node (ref "LS2") (pin "4") (pinfunction "1_4") (pintype "passive"))
    )
    (net (code "75") (name "unconnected-(LS3D-1-Pad4)") (class "Default")
      (node (ref "LS3") (pin "4") (pinfunction "1_4") (pintype "passive"))
    )
    (net (code "76") (name "unconnected-(LS4D-1-Pad4)") (class "Default")
      (node (ref "LS4") (pin "4") (pinfunction "1_4") (pintype "passive"))
    )
    (net (code "77") (name "unconnected-(LS5D-1-Pad4)") (class "Default")
      (node (ref "LS5") (pin "4") (pinfunction "1_4") (pintype "passive"))
    )
    (net (code "78") (name "unconnected-(LS6D-1-Pad4)") (class "Default")
      (node (ref "LS6") (pin "4") (pinfunction "1_4") (pintype "passive"))
    )
    (net (code "79") (name "unconnected-(LS7D-1-Pad4)") (class "Default")
      (node (ref "LS7") (pin "4") (pinfunction "1_4") (pintype "passive"))
    )
    (net (code "80") (name "unconnected-(LS8D-1-Pad4)") (class "Default")
      (node (ref "LS8") (pin "4") (pinfunction "1_4") (pintype "passive"))
    )
    (net (code "81") (name "unconnected-(LS9D-1-Pad4)") (class "Default")
      (node (ref "LS9") (pin "4") (pinfunction "1_4") (pintype "passive"))
    )
    (net (code "82") (name "unconnected-(LS10D-1-Pad4)") (class "Default")
      (node (ref "LS10") (pin "4") (pinfunction "1_4") (pintype "passive"))
    )
    (net (code "83") (name "unconnected-(MP6500_3-EN-PadENBL)") (class "Default")
      (node (ref "MP6500_3") (pin "ENBL") (pinfunction "EN_ENBL") (pintype "bidirectional"))
    )
    (net (code "84") (name "unconnected-(MP6500_3-FLT-PadFAULT)") (class "Default")
      (node (ref "MP6500_3") (pin "FAULT") (pinfunction "FLT_FAULT") (pintype "bidirectional"))
    )
    (net (code "85") (name "unconnected-(MP6500_3-PadMS1)") (class "Default")
      (node (ref "MP6500_3") (pin "MS1") (pinfunction "MS1_MS1") (pintype "bidirectional"))
    )
    (net (code "86") (name "unconnected-(MP6500_3-PadMS2)") (class "Default")
      (node (ref "MP6500_3") (pin "MS2") (pinfunction "MS2_MS2") (pintype "bidirectional"))
    )
    (net (code "87") (name "unconnected-(MP6500_4-EN-PadENBL)") (class "Default")
      (node (ref "MP6500_4") (pin "ENBL") (pinfunction "EN_ENBL") (pintype "bidirectional"))
    )
    (net (code "88") (name "unconnected-(MP6500_4-FLT-PadFAULT)") (class "Default")
      (node (ref "MP6500_4") (pin "FAULT") (pinfunction "FLT_FAULT") (pintype "bidirectional"))
    )
    (net (code "89") (name "unconnected-(MP6500_4-PadMS1)") (class "Default")
      (node (ref "MP6500_4") (pin "MS1") (pinfunction "MS1_MS1") (pintype "bidirectional"))
    )
    (net (code "90") (name "unconnected-(MP6500_4-PadMS2)") (class "Default")
      (node (ref "MP6500_4") (pin "MS2") (pinfunction "MS2_MS2") (pintype "bidirectional"))
    )
    (net (code "91") (name "unconnected-(POT1D-1-Pad4)") (class "Default")
      (node (ref "POT1") (pin "4") (pinfunction "1_4") (pintype "passive"))
    )
    (net (code "92") (name "unconnected-(POT2D-1-Pad4)") (class "Default")
      (node (ref "POT2") (pin "4") (pinfunction "1_4") (pintype "passive"))
    )
    (net (code "93") (name "unconnected-(POT3D-1-Pad4)") (class "Default")
      (node (ref "POT3") (pin "4") (pinfunction "1_4") (pintype "passive"))
    )
    (net (code "94") (name "unconnected-(POT4D-1-Pad4)") (class "Default")
      (node (ref "POT4") (pin "4") (pinfunction "1_4") (pintype "passive"))
    )
    (net (code "95") (name "unconnected-(POT5D-1-Pad4)") (class "Default")
      (node (ref "POT5") (pin "4") (pinfunction "1_4") (pintype "passive"))
    )
    (net (code "96") (name "unconnected-(POT6D-1-Pad4)") (class "Default")
      (node (ref "POT6") (pin "4") (pinfunction "1_4") (pintype "passive"))
    )
    (net (code "97") (name "unconnected-(TBVCC1C-1-Pad3)") (class "Default")
      (node (ref "TBVCC1") (pin "3") (pinfunction "1_3") (pintype "passive"))
    )
    (net (code "98") (name "unconnected-(TBVCC1D-1-Pad4)") (class "Default")
      (node (ref "TBVCC1") (pin "4") (pinfunction "1_4") (pintype "passive"))
    )
    (net (code "99") (name "unconnected-(TBVCC2C-1-Pad3)") (class "Default")
      (node (ref "TBVCC2") (pin "3") (pinfunction "1_3") (pintype "passive"))
    )
    (net (code "100") (name "unconnected-(TBVCC2D-1-Pad4)") (class "Default")
      (node (ref "TBVCC2") (pin "4") (pinfunction "1_4") (pintype "passive"))
    )
    (net (code "101") (name "unconnected-(TBVCC3C-1-Pad3)") (class "Default")
      (node (ref "TBVCC3") (pin "3") (pinfunction "1_3") (pintype "passive"))
    )
    (net (code "102") (name "unconnected-(TBVCC3D-1-Pad4)") (class "Default")
      (node (ref "TBVCC3") (pin "4") (pinfunction "1_4") (pintype "passive"))
    )
    (net (code "103") (name "unconnected-(TBVCC4C-1-Pad3)") (class "Default")
      (node (ref "TBVCC4") (pin "3") (pinfunction "1_3") (pintype "passive"))
    )
    (net (code "104") (name "unconnected-(TBVCC4D-1-Pad4)") (class "Default")
      (node (ref "TBVCC4") (pin "4") (pinfunction "1_4") (pintype "passive"))
    )
    (net (code "105") (name "unconnected-(TEENSY4.2-Pad3V3_2)") (class "Default")
      (node (ref "TEENSY4.2") (pin "3V3_2") (pinfunction "3V3_2_3V3_2") (pintype "bidirectional"))
    )
    (net (code "106") (name "unconnected-(TEENSY4.2-Pad13{slash}SCK)") (class "Default")
      (node (ref "TEENSY4.2") (pin "13/SCK") (pinfunction "13/SCK_13/SCK") (pintype "bidirectional"))
    )
    (net (code "107") (name "unconnected-(TEENSY4.2-Pad30)") (class "Default")
      (node (ref "TEENSY4.2") (pin "30") (pinfunction "30_30") (pintype "bidirectional"))
    )
    (net (code "108") (name "unconnected-(TEENSY4.2-Pad31{slash}A12)") (class "Default")
      (node (ref "TEENSY4.2") (pin "31/A12") (pinfunction "31/A12_31/A12") (pintype "bidirectional"))
    )
    (net (code "109") (name "unconnected-(TEENSY4.2-Pad32{slash}A13)") (class "Default")
      (node (ref "TEENSY4.2") (pin "32/A13") (pinfunction "32/A13_32/A13") (pintype "bidirectional"))
    )
    (net (code "110") (name "unconnected-(TEENSY4.2-Pad33{slash}A14)") (class "Default")
      (node (ref "TEENSY4.2") (pin "33/A14") (pinfunction "33/A14_33/A14") (pintype "bidirectional"))
    )
    (net (code "111") (name "unconnected-(TEENSY4.2-Pad34{slash}A15)") (class "Default")
      (node (ref "TEENSY4.2") (pin "34/A15") (pinfunction "34/A15_34/A15") (pintype "bidirectional"))
    )
    (net (code "112") (name "unconnected-(TEENSY4.2-Pad35{slash}A16)") (class "Default")
      (node (ref "TEENSY4.2") (pin "35/A16") (pinfunction "35/A16_35/A16") (pintype "bidirectional"))
    )
    (net (code "113") (name "unconnected-(TEENSY4.2-Pad36{slash}A17)") (class "Default")
      (node (ref "TEENSY4.2") (pin "36/A17") (pinfunction "36/A17_36/A17") (pintype "bidirectional"))
    )
    (net (code "114") (name "unconnected-(TEENSY4.2-Pad37{slash}A18)") (class "Default")
      (node (ref "TEENSY4.2") (pin "37/A18") (pinfunction "37/A18_37/A18") (pintype "bidirectional"))
    )
    (net (code "115") (name "unconnected-(TEENSY4.2-PadA10)") (class "Default")
      (node (ref "TEENSY4.2") (pin "A10") (pinfunction "A10_A10") (pintype "bidirectional"))
    )
    (net (code "116") (name "unconnected-(TEENSY4.2-PadA11)") (class "Default")
      (node (ref "TEENSY4.2") (pin "A11") (pinfunction "A11_A11") (pintype "bidirectional"))
    )
    (net (code "117") (name "unconnected-(TEENSY4.2-PadAGND)") (class "Default")
      (node (ref "TEENSY4.2") (pin "AGND") (pinfunction "AGND_AGND") (pintype "bidirectional"))
    )
    (net (code "118") (name "unconnected-(TEENSY4.2-PadAREF)") (class "Default")
      (node (ref "TEENSY4.2") (pin "AREF") (pinfunction "AREF_AREF") (pintype "bidirectional"))
    )
    (net (code "119") (name "unconnected-(TEENSY4.2-PadGND2)") (class "Default")
      (node (ref "TEENSY4.2") (pin "GND2") (pinfunction "GND2_GND2") (pintype "bidirectional"))
    )
    (net (code "120") (name "unconnected-(TEENSY4.2-PadGND3)") (class "Default")
      (node (ref "TEENSY4.2") (pin "GND3") (pinfunction "GND3_GND3") (pintype "bidirectional"))
    )
    (net (code "121") (name "unconnected-(TEENSY4.2-PadPROG)") (class "Default")
      (node (ref "TEENSY4.2") (pin "PROG") (pinfunction "PROG_PROG") (pintype "bidirectional"))
    )
    (net (code "122") (name "unconnected-(TEENSY4.2-PadRESET)") (class "Default")
      (node (ref "TEENSY4.2") (pin "RESET") (pinfunction "RESET_RESET") (pintype "bidirectional"))
    )
    (net (code "123") (name "unconnected-(TEENSY4.2-PadU5V)") (class "Default")
      (node (ref "TEENSY4.2") (pin "U5V") (pinfunction "U5V_U5V") (pintype "bidirectional"))
    )
    (net (code "124") (name "unconnected-(TEENSY4.2-PadUD+)") (class "Default")
      (node (ref "TEENSY4.2") (pin "UD+") (pinfunction "UD+_UD+") (pintype "bidirectional"))
    )
    (net (code "125") (name "unconnected-(TEENSY4.2-PadUD-)") (class "Default")
      (node (ref "TEENSY4.2") (pin "UD-") (pinfunction "UD-_UD-") (pintype "bidirectional"))
    )
    (net (code "126") (name "unconnected-(TEENSY4.2-PadUGND1)") (class "Default")
      (node (ref "TEENSY4.2") (pin "UGND1") (pinfunction "UGND1_UGND1") (pintype "bidirectional"))
    )
    (net (code "127") (name "unconnected-(TEENSY4.2-PadUGND2)") (class "Default")
      (node (ref "TEENSY4.2") (pin "UGND2") (pinfunction "UGND2_UGND2") (pintype "bidirectional"))
    )
    (net (code "128") (name "unconnected-(TEENSY4.2-PadVBAT)") (class "Default")
      (node (ref "TEENSY4.2") (pin "VBAT") (pinfunction "VBAT_VBAT") (pintype "bidirectional"))
    )
    (net (code "129") (name "unconnected-(TEENSY4.2-PadVUSB)") (class "Default")
      (node (ref "TEENSY4.2") (pin "VUSB") (pinfunction "VUSB_VUSB") (pintype "bidirectional"))
    )
  )
)
